# little-endian.net
KiCad netlist of a schematic drawn in EAGLE
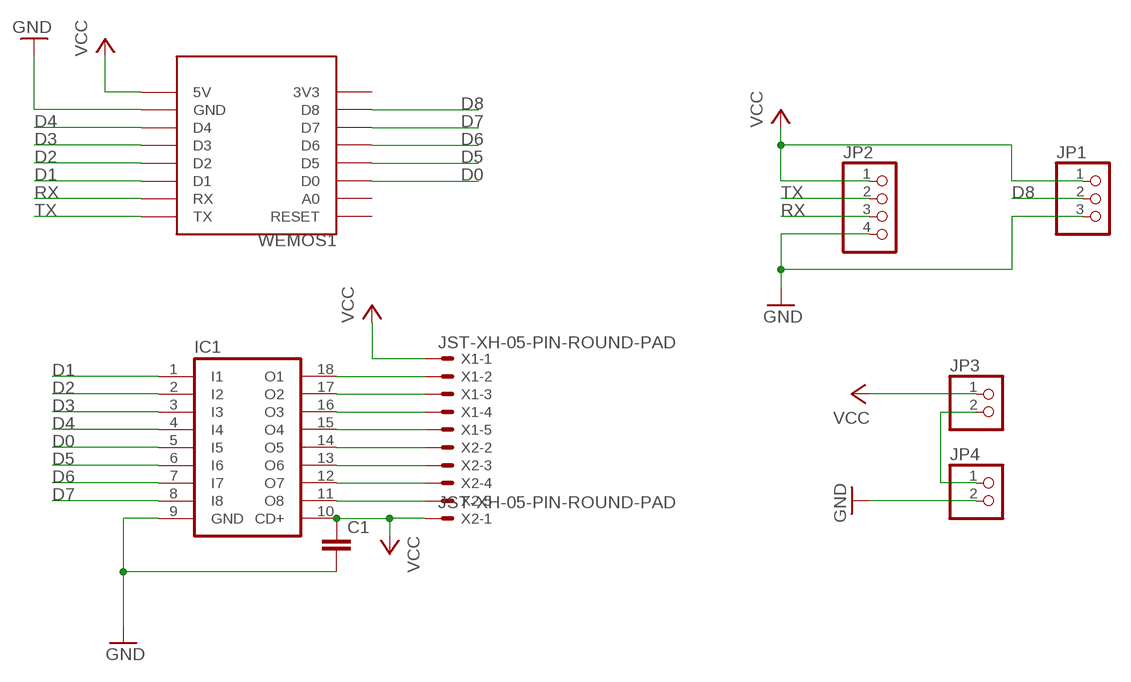
[diagram p0: schematic, sheet 1]

(export (version "E")
  (design (tool "Eeschema 10.0.6"))
  (components
    (comp (ref "C1")
      (value "C-EU050-030X075")
      (footprint "eagle-import:C050-030X075")
      (libsource (lib "eagle-import") (part "C-EU050-030X075"))
    )
    (comp (ref "IC1")
      (value "ULN2803A")
      (footprint "eagle-import:DIL18")
      (libsource (lib "eagle-import") (part "ULN2803A"))
    )
    (comp (ref "JP1")
      (value "PINHD-1X3")
      (footprint "eagle-import:1X03")
      (libsource (lib "eagle-import") (part "PINHD-1X3"))
    )
    (comp (ref "JP2")
      (value "PINHD-1X4")
      (footprint "eagle-import:1X04")
      (libsource (lib "eagle-import") (part "PINHD-1X4"))
    )
    (comp (ref "JP3")
      (value "PINHD-1X2")
      (footprint "eagle-import:1X02")
      (libsource (lib "eagle-import") (part "PINHD-1X2"))
    )
    (comp (ref "JP4")
      (value "PINHD-1X2")
      (footprint "eagle-import:1X02")
      (libsource (lib "eagle-import") (part "PINHD-1X2"))
    )
    (comp (ref "WEMOS1")
      (value "WEMOS-D1-MINI")
      (footprint "eagle-import:WEMOS-D1-MINI")
      (libsource (lib "eagle-import") (part "WEMOS-D1-MINI"))
    )
    (comp (ref "X1")
      (value "JST-XH-05-PIN-ROUND-PAD")
      (footprint "eagle-import:JST-XH-05-PACKAGE-ROUND-PAD")
      (libsource (lib "eagle-import") (part "JST-XH-05-PIN-ROUND-PAD"))
    )
    (comp (ref "X2")
      (value "JST-XH-05-PIN-ROUND-PAD")
      (footprint "eagle-import:JST-XH-05-PACKAGE-ROUND-PAD")
      (libsource (lib "eagle-import") (part "JST-XH-05-PIN-ROUND-PAD"))
    )
  )
  (nets
    (net (code "1") (name "/D0") (class "Default")
      (node (ref "IC1") (pin "5") (pinfunction "I5_5") (pintype "input"))
      (node (ref "WEMOS1") (pin "D0") (pinfunction "D0_D0") (pintype "bidirectional"))
    )
    (net (code "2") (name "/D1") (class "Default")
      (node (ref "IC1") (pin "1") (pinfunction "I1_1") (pintype "input"))
      (node (ref "WEMOS1") (pin "D1") (pinfunction "D1_D1") (pintype "bidirectional"))
    )
    (net (code "3") (name "/D2") (class "Default")
      (node (ref "IC1") (pin "2") (pinfunction "I2_2") (pintype "input"))
      (node (ref "WEMOS1") (pin "D2") (pinfunction "D2_D2") (pintype "bidirectional"))
    )
    (net (code "4") (name "/D3") (class "Default")
      (node (ref "IC1") (pin "3") (pinfunction "I3_3") (pintype "input"))
      (node (ref "WEMOS1") (pin "D3") (pinfunction "D3_D3") (pintype "bidirectional"))
    )
    (net (code "5") (name "/D4") (class "Default")
      (node (ref "IC1") (pin "4") (pinfunction "I4_4") (pintype "input"))
      (node (ref "WEMOS1") (pin "D4") (pinfunction "D4_D4") (pintype "bidirectional"))
    )
    (net (code "6") (name "/D5") (class "Default")
      (node (ref "IC1") (pin "6") (pinfunction "I6_6") (pintype "input"))
      (node (ref "WEMOS1") (pin "D5") (pinfunction "D5_D5") (pintype "bidirectional"))
    )
    (net (code "7") (name "/D6") (class "Default")
      (node (ref "IC1") (pin "7") (pinfunction "I7_7") (pintype "input"))
      (node (ref "WEMOS1") (pin "D6") (pinfunction "D6_D6") (pintype "bidirectional"))
    )
    (net (code "8") (name "/D7") (class "Default")
      (node (ref "IC1") (pin "8") (pinfunction "I8_8") (pintype "input"))
      (node (ref "WEMOS1") (pin "D7") (pinfunction "D7_D7") (pintype "bidirectional"))
    )
    (net (code "9") (name "/D8") (class "Default")
      (node (ref "JP1") (pin "2") (pinfunction "2_2") (pintype "passive"))
      (node (ref "WEMOS1") (pin "D8") (pinfunction "D8_D8") (pintype "bidirectional"))
    )
    (net (code "10") (name "/RX") (class "Default")
      (node (ref "JP2") (pin "3") (pinfunction "3_3") (pintype "passive"))
      (node (ref "WEMOS1") (pin "RX") (pinfunction "RX_RX") (pintype "bidirectional"))
    )
    (net (code "11") (name "/TX") (class "Default")
      (node (ref "JP2") (pin "2") (pinfunction "2_2") (pintype "passive"))
      (node (ref "WEMOS1") (pin "TX") (pinfunction "TX_TX") (pintype "bidirectional"))
    )
    (net (code "12") (name "GND") (class "Default")
      (node (ref "C1") (pin "2") (pinfunction "2_2") (pintype "passive"))
      (node (ref "IC1") (pin "9") (pinfunction "GND_9") (pintype "power_in"))
      (node (ref "JP1") (pin "3") (pinfunction "3_3") (pintype "passive"))
      (node (ref "JP2") (pin "4") (pinfunction "4_4") (pintype "passive"))
      (node (ref "JP4") (pin "2") (pinfunction "2_2") (pintype "passive"))
      (node (ref "WEMOS1") (pin "GND") (pinfunction "GND_GND") (pintype "bidirectional"))
    )
    (net (code "13") (name "Net-(IC1-O1)") (class "Default")
      (node (ref "IC1") (pin "18") (pinfunction "O1_18") (pintype "open_collector"))
      (node (ref "X1") (pin "2") (pinfunction "S_2") (pintype "passive"))
    )
    (net (code "14") (name "Net-(IC1-O2)") (class "Default")
      (node (ref "IC1") (pin "17") (pinfunction "O2_17") (pintype "open_collector"))
      (node (ref "X1") (pin "3") (pinfunction "S_3") (pintype "passive"))
    )
    (net (code "15") (name "Net-(IC1-O3)") (class "Default")
      (node (ref "IC1") (pin "16") (pinfunction "O3_16") (pintype "open_collector"))
      (node (ref "X1") (pin "4") (pinfunction "S_4") (pintype "passive"))
    )
    (net (code "16") (name "Net-(IC1-O4)") (class "Default")
      (node (ref "IC1") (pin "15") (pinfunction "O4_15") (pintype "open_collector"))
      (node (ref "X1") (pin "5") (pinfunction "S_5") (pintype "passive"))
    )
    (net (code "17") (name "Net-(IC1-O5)") (class "Default")
      (node (ref "IC1") (pin "14") (pinfunction "O5_14") (pintype "open_collector"))
      (node (ref "X2") (pin "2") (pinfunction "S_2") (pintype "passive"))
    )
    (net (code "18") (name "Net-(IC1-O6)") (class "Default")
      (node (ref "IC1") (pin "13") (pinfunction "O6_13") (pintype "open_collector"))
      (node (ref "X2") (pin "3") (pinfunction "S_3") (pintype "passive"))
    )
    (net (code "19") (name "Net-(IC1-O7)") (class "Default")
      (node (ref "IC1") (pin "12") (pinfunction "O7_12") (pintype "open_collector"))
      (node (ref "X2") (pin "4") (pinfunction "S_4") (pintype "passive"))
    )
    (net (code "20") (name "Net-(IC1-O8)") (class "Default")
      (node (ref "IC1") (pin "11") (pinfunction "O8_11") (pintype "open_collector"))
      (node (ref "X2") (pin "5") (pinfunction "S_5") (pintype "passive"))
    )
    (net (code "21") (name "Net-(JP3-Pad2)") (class "Default")
      (node (ref "JP3") (pin "2") (pinfunction "2_2") (pintype "passive"))
      (node (ref "JP4") (pin "1") (pinfunction "1_1") (pintype "passive"))
    )
    (net (code "22") (name "VCC") (class "Default")
      (node (ref "C1") (pin "1") (pinfunction "1_1") (pintype "passive"))
      (node (ref "IC1") (pin "10") (pinfunction "CD+_10") (pintype "passive"))
      (node (ref "JP1") (pin "1") (pinfunction "1_1") (pintype "passive"))
      (node (ref "JP2") (pin "1") (pinfunction "1_1") (pintype "passive"))
      (node (ref "JP3") (pin "1") (pinfunction "1_1") (pintype "passive"))
      (node (ref "WEMOS1") (pin "5V") (pinfunction "5V_5V") (pintype "bidirectional"))
      (node (ref "X1") (pin "1") (pinfunction "S_1") (pintype "passive"))
      (node (ref "X2") (pin "1") (pinfunction "S_1") (pintype "passive"))
    )
    (net (code "23") (name "unconnected-(WEMOS1-Pad3V3)") (class "Default")
      (node (ref "WEMOS1") (pin "3V3") (pinfunction "3V3_3V3") (pintype "bidirectional"))
    )
    (net (code "24") (name "unconnected-(WEMOS1-PadA0)") (class "Default")
      (node (ref "WEMOS1") (pin "A0") (pinfunction "A0_A0") (pintype "bidirectional"))
    )
    (net (code "25") (name "unconnected-(WEMOS1-PadRESET)") (class "Default")
      (node (ref "WEMOS1") (pin "RESET") (pinfunction "RESET_RESET") (pintype "bidirectional"))
    )
  )
)
